# BB_schematic.net
KiCad netlist of a schematic drawn in EAGLE
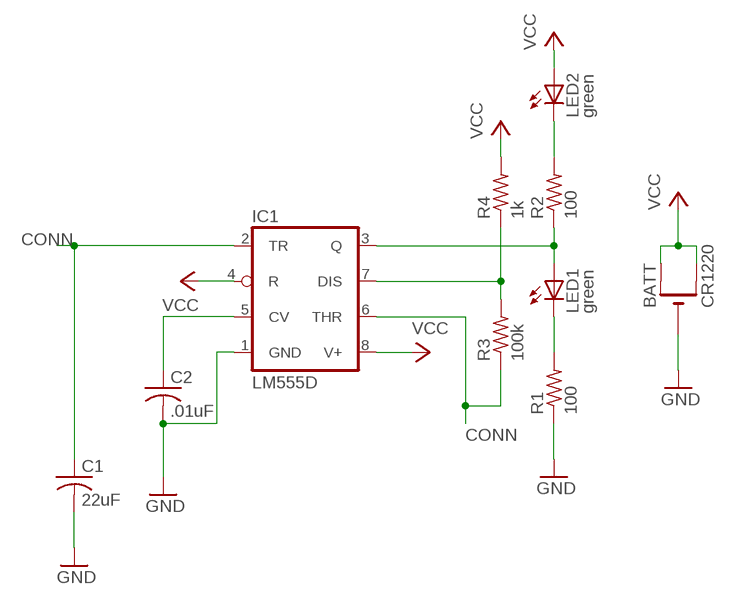
[diagram p0: schematic, sheet 1]

(export (version "E")
  (design (tool "Eeschema 10.0.6"))
  (components
    (comp (ref "BATT")
      (value "CR1220")
      (footprint "eagle-import:CR1220-SMD")
      (fields (field (name "MPN") "3080"))
      (libsource (lib "eagle-import") (part "CR1220SMT"))
    )
    (comp (ref "C1")
      (value "22uF")
      (footprint "eagle-import:C0805")
      (fields (field (name "MPN") "C2012X5R0J226M125AC"))
      (libsource (lib "eagle-import") (part "C-USC0805"))
    )
    (comp (ref "C2")
      (value ".01uF")
      (footprint "eagle-import:C0805")
      (fields (field (name "MPN") "MC0805B103M500CT"))
      (libsource (lib "eagle-import") (part "C-USC0805"))
    )
    (comp (ref "IC1")
      (value "LM555D")
      (footprint "eagle-import:SO08")
      (fields (field (name "MF") "TEXAS INSTRUMENTS") (field (name "MPN") "TLC555ID"))
      (libsource (lib "eagle-import") (part "555DLM"))
    )
    (comp (ref "LED1")
      (value "green")
      (footprint "eagle-import:CHIPLED_0805")
      (fields (field (name "MPN") "5988170107F"))
      (libsource (lib "eagle-import") (part "LEDCHIPLED_0805"))
    )
    (comp (ref "LED2")
      (value "green")
      (footprint "eagle-import:CHIPLED_0805")
      (fields (field (name "MPN") "5988170107F"))
      (libsource (lib "eagle-import") (part "LEDCHIPLED_0805"))
    )
    (comp (ref "R1")
      (value "100")
      (footprint "eagle-import:R0805")
      (fields (field (name "MPN") "MCTF0805BTC1000"))
      (libsource (lib "eagle-import") (part "R-US_R0805"))
    )
    (comp (ref "R2")
      (value "100")
      (footprint "eagle-import:R0805")
      (fields (field (name "MPN") "MCTF0805BTC1000"))
      (libsource (lib "eagle-import") (part "R-US_R0805"))
    )
    (comp (ref "R3")
      (value "100k")
      (footprint "eagle-import:R0805")
      (fields (field (name "MF") "VISHAY/DALE") (field (name "MPN") "CRCW0805100KFKTA"))
      (libsource (lib "eagle-import") (part "R-US_R0805"))
    )
    (comp (ref "R4")
      (value "1k")
      (footprint "eagle-import:R0805")
      (fields (field (name "MPN") "MCTF0805BTC1001"))
      (libsource (lib "eagle-import") (part "R-US_R0805"))
    )
  )
  (nets
    (net (code "1") (name "/CONN") (class "Default")
      (node (ref "C1") (pin "1") (pinfunction "1_1") (pintype "passive"))
      (node (ref "IC1") (pin "2") (pinfunction "TR_2") (pintype "input"))
      (node (ref "IC1") (pin "6") (pinfunction "THR_6") (pintype "input"))
      (node (ref "R3") (pin "1") (pinfunction "1_1") (pintype "passive"))
    )
    (net (code "2") (name "GND") (class "Default")
      (node (ref "BATT") (pin "-") (pinfunction "-_-") (pintype "passive"))
      (node (ref "C1") (pin "2") (pinfunction "2_2") (pintype "passive"))
      (node (ref "C2") (pin "2") (pinfunction "2_2") (pintype "passive"))
      (node (ref "IC1") (pin "1") (pinfunction "GND_1") (pintype "power_in"))
      (node (ref "R1") (pin "1") (pinfunction "1_1") (pintype "passive"))
    )
    (net (code "3") (name "Net-(IC1-CV)") (class "Default")
      (node (ref "C2") (pin "1") (pinfunction "1_1") (pintype "passive"))
      (node (ref "IC1") (pin "5") (pinfunction "CV_5") (pintype "input"))
    )
    (net (code "4") (name "Net-(IC1-DIS)") (class "Default")
      (node (ref "IC1") (pin "7") (pinfunction "DIS_7") (pintype "input"))
      (node (ref "R3") (pin "2") (pinfunction "2_2") (pintype "passive"))
      (node (ref "R4") (pin "1") (pinfunction "1_1") (pintype "passive"))
    )
    (net (code "5") (name "Net-(IC1-Q)") (class "Default")
      (node (ref "IC1") (pin "3") (pinfunction "Q_3") (pintype "output"))
      (node (ref "LED1") (pin "A") (pinfunction "A_A") (pintype "passive"))
      (node (ref "R2") (pin "1") (pinfunction "1_1") (pintype "passive"))
    )
    (net (code "6") (name "Net-(LED1-PadC)") (class "Default")
      (node (ref "LED1") (pin "C") (pinfunction "C_C") (pintype "passive"))
      (node (ref "R1") (pin "2") (pinfunction "2_2") (pintype "passive"))
    )
    (net (code "7") (name "Net-(LED2-PadC)") (class "Default")
      (node (ref "LED2") (pin "C") (pinfunction "C_C") (pintype "passive"))
      (node (ref "R2") (pin "2") (pinfunction "2_2") (pintype "passive"))
    )
    (net (code "8") (name "VCC") (class "Default")
      (node (ref "BATT") (pin "+$1") (pinfunction "+_+$1") (pintype "passive"))
      (node (ref "BATT") (pin "+$2") (pinfunction "+1_+$2") (pintype "passive"))
      (node (ref "IC1") (pin "4") (pinfunction "R_4") (pintype "input"))
      (node (ref "IC1") (pin "8") (pinfunction "V+_8") (pintype "power_in"))
      (node (ref "LED2") (pin "A") (pinfunction "A_A") (pintype "passive"))
      (node (ref "R4") (pin "2") (pinfunction "2_2") (pintype "passive"))
    )
  )
)
